# FR5969.net
KiCad netlist of a schematic drawn in EAGLE
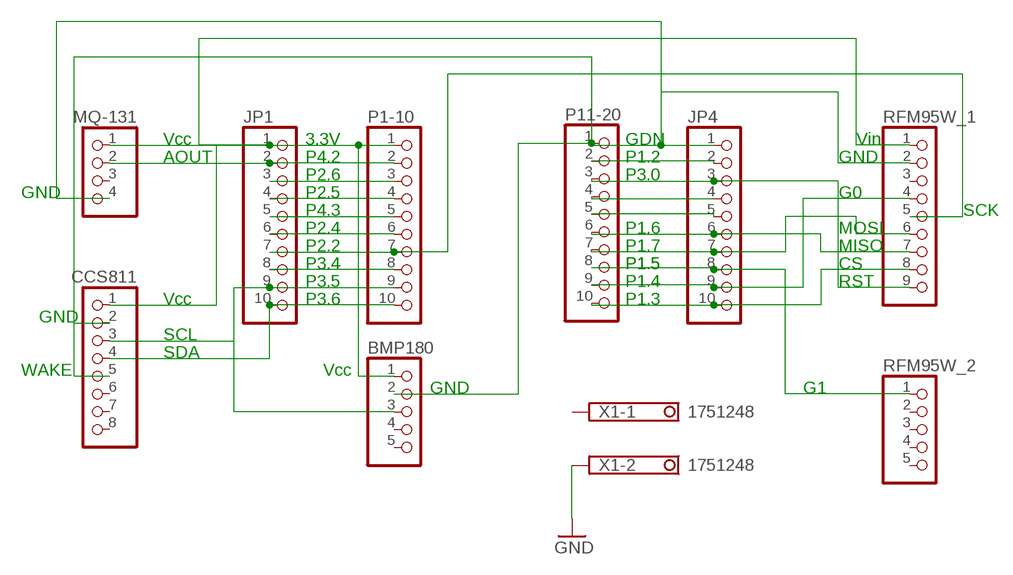
[diagram p0: schematic, sheet 1]

(export (version "E")
  (design (tool "Eeschema 10.0.6"))
  (components
    (comp (ref "BMP180")
      (value "PINHD-1X5")
      (footprint "eagle-import:1X05")
      (libsource (lib "eagle-import") (part "PINHD-1X5"))
    )
    (comp (ref "CCS811")
      (value "PINHD-1X8")
      (footprint "eagle-import:1X08")
      (libsource (lib "eagle-import") (part "PINHD-1X8"))
    )
    (comp (ref "JP1")
      (value "PINHD-1X10")
      (footprint "eagle-import:1X10")
      (libsource (lib "eagle-import") (part "PINHD-1X10"))
    )
    (comp (ref "JP4")
      (value "PINHD-1X10")
      (footprint "eagle-import:1X10")
      (libsource (lib "eagle-import") (part "PINHD-1X10"))
    )
    (comp (ref "MQ-131")
      (value "PINHD-1X4")
      (footprint "eagle-import:1X04")
      (libsource (lib "eagle-import") (part "PINHD-1X4"))
    )
    (comp (ref "P1-10")
      (value "PINHD-1X10")
      (footprint "eagle-import:1X10")
      (libsource (lib "eagle-import") (part "PINHD-1X10"))
    )
    (comp (ref "P11-20")
      (value "PINHD-1X10")
      (footprint "eagle-import:1X10")
      (libsource (lib "eagle-import") (part "PINHD-1X10"))
    )
    (comp (ref "RFM95W_1")
      (value "PINHD-1X9")
      (footprint "eagle-import:1X09")
      (libsource (lib "eagle-import") (part "PINHD-1X9"))
    )
    (comp (ref "RFM95W_2")
      (value "PINHD-1X5")
      (footprint "eagle-import:1X05")
      (libsource (lib "eagle-import") (part "PINHD-1X5"))
    )
    (comp (ref "X1")
      (value "1751248")
      (footprint "eagle-import:1751248")
      (libsource (lib "eagle-import") (part "1751248"))
    )
  )
  (nets
    (net (code "1") (name "GND") (class "Default")
      (node (ref "X1") (pin "2") (pinfunction "K_2") (pintype "passive"))
    )
    (net (code "2") (name "Net-(BMP180-Pad1)") (class "Default")
      (node (ref "BMP180") (pin "1") (pinfunction "1_1") (pintype "passive"))
      (node (ref "CCS811") (pin "1") (pinfunction "1_1") (pintype "passive"))
      (node (ref "JP1") (pin "1") (pinfunction "1_1") (pintype "passive"))
      (node (ref "MQ-131") (pin "1") (pinfunction "1_1") (pintype "passive"))
      (node (ref "P1-10") (pin "1") (pinfunction "1_1") (pintype "passive"))
      (node (ref "RFM95W_1") (pin "1") (pinfunction "1_1") (pintype "passive"))
    )
    (net (code "3") (name "Net-(BMP180-Pad2)") (class "Default")
      (node (ref "BMP180") (pin "2") (pinfunction "2_2") (pintype "passive"))
      (node (ref "CCS811") (pin "2") (pinfunction "2_2") (pintype "passive"))
      (node (ref "CCS811") (pin "5") (pinfunction "5_5") (pintype "passive"))
      (node (ref "JP4") (pin "1") (pinfunction "1_1") (pintype "passive"))
      (node (ref "MQ-131") (pin "4") (pinfunction "4_4") (pintype "passive"))
      (node (ref "P11-20") (pin "1") (pinfunction "1_1") (pintype "passive"))
      (node (ref "RFM95W_1") (pin "2") (pinfunction "2_2") (pintype "passive"))
    )
    (net (code "4") (name "Net-(BMP180-Pad3)") (class "Default")
      (node (ref "BMP180") (pin "3") (pinfunction "3_3") (pintype "passive"))
      (node (ref "CCS811") (pin "3") (pinfunction "3_3") (pintype "passive"))
      (node (ref "JP1") (pin "9") (pinfunction "9_9") (pintype "passive"))
      (node (ref "P1-10") (pin "9") (pinfunction "9_9") (pintype "passive"))
    )
    (net (code "5") (name "Net-(CCS811-Pad4)") (class "Default")
      (node (ref "CCS811") (pin "4") (pinfunction "4_4") (pintype "passive"))
      (node (ref "JP1") (pin "10") (pinfunction "10_10") (pintype "passive"))
      (node (ref "P1-10") (pin "10") (pinfunction "10_10") (pintype "passive"))
    )
    (net (code "6") (name "Net-(JP1-Pad2)") (class "Default")
      (node (ref "JP1") (pin "2") (pinfunction "2_2") (pintype "passive"))
      (node (ref "MQ-131") (pin "2") (pinfunction "2_2") (pintype "passive"))
      (node (ref "P1-10") (pin "2") (pinfunction "2_2") (pintype "passive"))
    )
    (net (code "7") (name "Net-(JP1-Pad3)") (class "Default")
      (node (ref "JP1") (pin "3") (pinfunction "3_3") (pintype "passive"))
      (node (ref "P1-10") (pin "3") (pinfunction "3_3") (pintype "passive"))
    )
    (net (code "8") (name "Net-(JP1-Pad4)") (class "Default")
      (node (ref "JP1") (pin "4") (pinfunction "4_4") (pintype "passive"))
      (node (ref "P1-10") (pin "4") (pinfunction "4_4") (pintype "passive"))
    )
    (net (code "9") (name "Net-(JP1-Pad5)") (class "Default")
      (node (ref "JP1") (pin "5") (pinfunction "5_5") (pintype "passive"))
      (node (ref "P1-10") (pin "5") (pinfunction "5_5") (pintype "passive"))
    )
    (net (code "10") (name "Net-(JP1-Pad6)") (class "Default")
      (node (ref "JP1") (pin "6") (pinfunction "6_6") (pintype "passive"))
      (node (ref "P1-10") (pin "6") (pinfunction "6_6") (pintype "passive"))
    )
    (net (code "11") (name "Net-(JP1-Pad7)") (class "Default")
      (node (ref "JP1") (pin "7") (pinfunction "7_7") (pintype "passive"))
      (node (ref "P1-10") (pin "7") (pinfunction "7_7") (pintype "passive"))
      (node (ref "RFM95W_1") (pin "5") (pinfunction "5_5") (pintype "passive"))
    )
    (net (code "12") (name "Net-(JP1-Pad8)") (class "Default")
      (node (ref "JP1") (pin "8") (pinfunction "8_8") (pintype "passive"))
      (node (ref "P1-10") (pin "8") (pinfunction "8_8") (pintype "passive"))
    )
    (net (code "13") (name "Net-(JP4-Pad2)") (class "Default")
      (node (ref "JP4") (pin "2") (pinfunction "2_2") (pintype "passive"))
      (node (ref "P11-20") (pin "2") (pinfunction "2_2") (pintype "passive"))
    )
    (net (code "14") (name "Net-(JP4-Pad3)") (class "Default")
      (node (ref "JP4") (pin "3") (pinfunction "3_3") (pintype "passive"))
      (node (ref "P11-20") (pin "3") (pinfunction "3_3") (pintype "passive"))
      (node (ref "RFM95W_1") (pin "9") (pinfunction "9_9") (pintype "passive"))
    )
    (net (code "15") (name "Net-(JP4-Pad4)") (class "Default")
      (node (ref "JP4") (pin "4") (pinfunction "4_4") (pintype "passive"))
      (node (ref "P11-20") (pin "4") (pinfunction "4_4") (pintype "passive"))
    )
    (net (code "16") (name "Net-(JP4-Pad5)") (class "Default")
      (node (ref "JP4") (pin "5") (pinfunction "5_5") (pintype "passive"))
      (node (ref "P11-20") (pin "5") (pinfunction "5_5") (pintype "passive"))
    )
    (net (code "17") (name "Net-(JP4-Pad6)") (class "Default")
      (node (ref "JP4") (pin "6") (pinfunction "6_6") (pintype "passive"))
      (node (ref "P11-20") (pin "6") (pinfunction "6_6") (pintype "passive"))
      (node (ref "RFM95W_1") (pin "7") (pinfunction "7_7") (pintype "passive"))
    )
    (net (code "18") (name "Net-(JP4-Pad7)") (class "Default")
      (node (ref "JP4") (pin "7") (pinfunction "7_7") (pintype "passive"))
      (node (ref "P11-20") (pin "7") (pinfunction "7_7") (pintype "passive"))
      (node (ref "RFM95W_1") (pin "6") (pinfunction "6_6") (pintype "passive"))
    )
    (net (code "19") (name "Net-(JP4-Pad8)") (class "Default")
      (node (ref "JP4") (pin "8") (pinfunction "8_8") (pintype "passive"))
      (node (ref "P11-20") (pin "8") (pinfunction "8_8") (pintype "passive"))
      (node (ref "RFM95W_2") (pin "1") (pinfunction "1_1") (pintype "passive"))
    )
    (net (code "20") (name "Net-(JP4-Pad9)") (class "Default")
      (node (ref "JP4") (pin "9") (pinfunction "9_9") (pintype "passive"))
      (node (ref "P11-20") (pin "9") (pinfunction "9_9") (pintype "passive"))
      (node (ref "RFM95W_1") (pin "4") (pinfunction "4_4") (pintype "passive"))
    )
    (net (code "21") (name "Net-(JP4-Pad10)") (class "Default")
      (node (ref "JP4") (pin "10") (pinfunction "10_10") (pintype "passive"))
      (node (ref "P11-20") (pin "10") (pinfunction "10_10") (pintype "passive"))
      (node (ref "RFM95W_1") (pin "8") (pinfunction "8_8") (pintype "passive"))
    )
    (net (code "22") (name "unconnected-(BMP180-Pad4)") (class "Default")
      (node (ref "BMP180") (pin "4") (pinfunction "4_4") (pintype "passive"))
    )
    (net (code "23") (name "unconnected-(BMP180-Pad5)") (class "Default")
      (node (ref "BMP180") (pin "5") (pinfunction "5_5") (pintype "passive"))
    )
    (net (code "24") (name "unconnected-(CCS811-Pad6)") (class "Default")
      (node (ref "CCS811") (pin "6") (pinfunction "6_6") (pintype "passive"))
    )
    (net (code "25") (name "unconnected-(CCS811-Pad7)") (class "Default")
      (node (ref "CCS811") (pin "7") (pinfunction "7_7") (pintype "passive"))
    )
    (net (code "26") (name "unconnected-(CCS811-Pad8)") (class "Default")
      (node (ref "CCS811") (pin "8") (pinfunction "8_8") (pintype "passive"))
    )
    (net (code "27") (name "unconnected-(MQ-131-Pad3)") (class "Default")
      (node (ref "MQ-131") (pin "3") (pinfunction "3_3") (pintype "passive"))
    )
    (net (code "28") (name "unconnected-(RFM95W_1-Pad3)") (class "Default")
      (node (ref "RFM95W_1") (pin "3") (pinfunction "3_3") (pintype "passive"))
    )
    (net (code "29") (name "unconnected-(RFM95W_2-Pad2)") (class "Default")
      (node (ref "RFM95W_2") (pin "2") (pinfunction "2_2") (pintype "passive"))
    )
    (net (code "30") (name "unconnected-(RFM95W_2-Pad3)") (class "Default")
      (node (ref "RFM95W_2") (pin "3") (pinfunction "3_3") (pintype "passive"))
    )
    (net (code "31") (name "unconnected-(RFM95W_2-Pad4)") (class "Default")
      (node (ref "RFM95W_2") (pin "4") (pinfunction "4_4") (pintype "passive"))
    )
    (net (code "32") (name "unconnected-(RFM95W_2-Pad5)") (class "Default")
      (node (ref "RFM95W_2") (pin "5") (pinfunction "5_5") (pintype "passive"))
    )
    (net (code "33") (name "unconnected-(X1A-K-Pad1)") (class "Default")
      (node (ref "X1") (pin "1") (pinfunction "K_1") (pintype "passive"))
    )
  )
)
